# Ring_3_A.net
KiCad netlist of a schematic drawn in Altium Designer
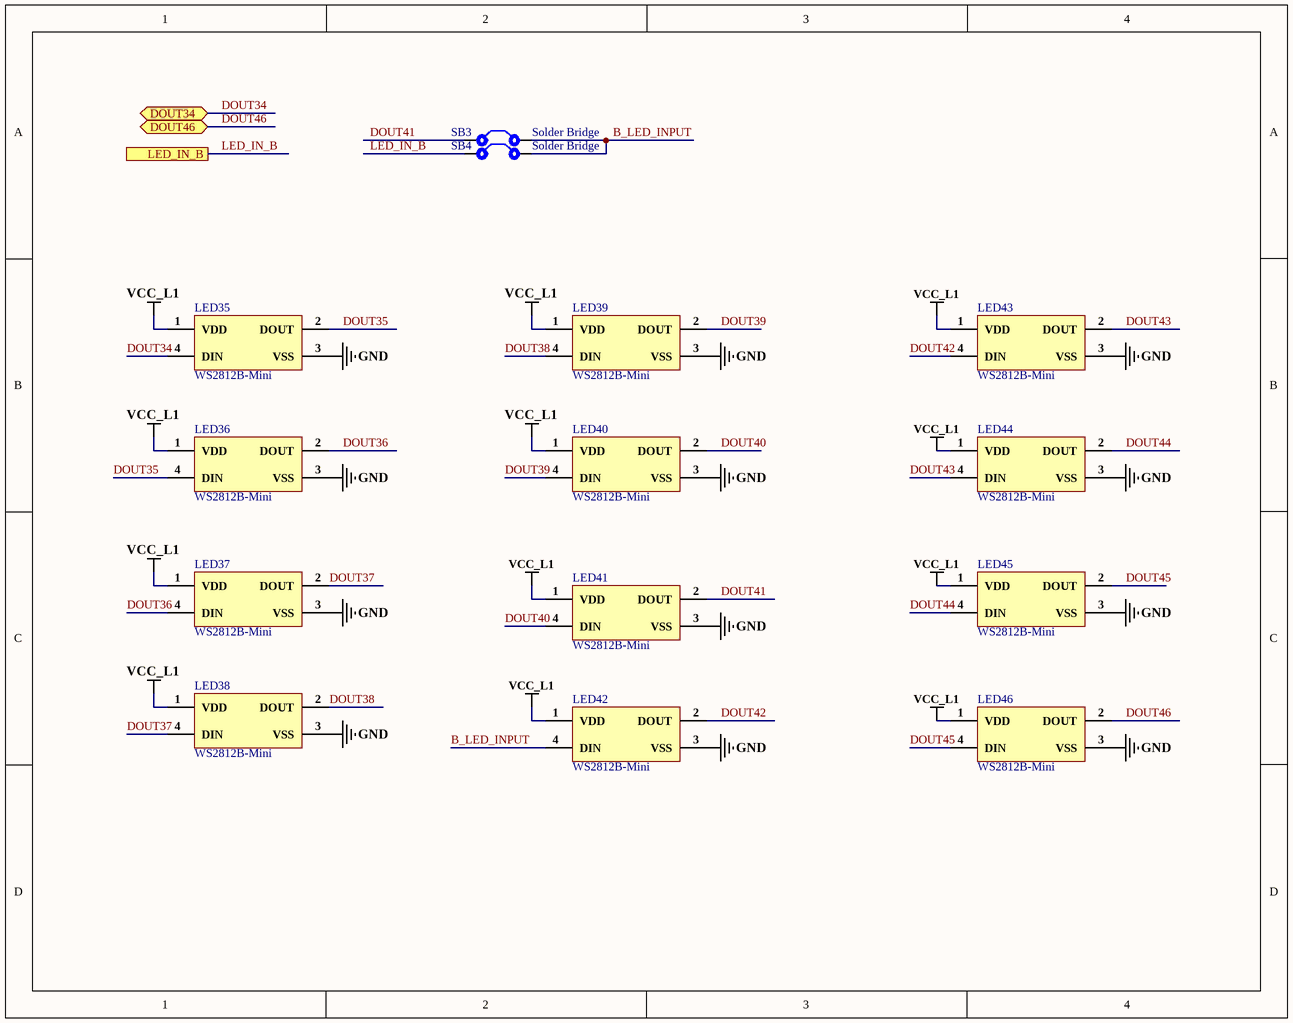
[diagram p0: Ring 3_A.SchDoc]

(export (version "E")
  (design (tool "Eeschema 10.0.6"))
  (components
    (comp (ref "LED35")
      (value "WS2812B-Mini")
      (footprint "WS2812B-Mini")
      (description "SMD,3.5x3.5mm Light Emitting Diodes (LED) RoHS")
      (fields (field (name "MANUFACTURER") "Worldsemi"))
      (libsource (lib "TT_IntLib") (part "WS2812B-Mini"))
    )
    (comp (ref "LED36")
      (value "WS2812B-Mini")
      (footprint "WS2812B-Mini")
      (description "SMD,3.5x3.5mm Light Emitting Diodes (LED) RoHS")
      (fields (field (name "MANUFACTURER") "Worldsemi"))
      (libsource (lib "TT_IntLib") (part "WS2812B-Mini"))
    )
    (comp (ref "LED37")
      (value "WS2812B-Mini")
      (footprint "WS2812B-Mini")
      (description "SMD,3.5x3.5mm Light Emitting Diodes (LED) RoHS")
      (fields (field (name "MANUFACTURER") "Worldsemi"))
      (libsource (lib "TT_IntLib") (part "WS2812B-Mini"))
    )
    (comp (ref "LED38")
      (value "WS2812B-Mini")
      (footprint "WS2812B-Mini")
      (description "SMD,3.5x3.5mm Light Emitting Diodes (LED) RoHS")
      (fields (field (name "MANUFACTURER") "Worldsemi"))
      (libsource (lib "TT_IntLib") (part "WS2812B-Mini"))
    )
    (comp (ref "LED39")
      (value "WS2812B-Mini")
      (footprint "WS2812B-Mini")
      (description "SMD,3.5x3.5mm Light Emitting Diodes (LED) RoHS")
      (fields (field (name "MANUFACTURER") "Worldsemi"))
      (libsource (lib "TT_IntLib") (part "WS2812B-Mini"))
    )
    (comp (ref "LED40")
      (value "WS2812B-Mini")
      (footprint "WS2812B-Mini")
      (description "SMD,3.5x3.5mm Light Emitting Diodes (LED) RoHS")
      (fields (field (name "MANUFACTURER") "Worldsemi"))
      (libsource (lib "TT_IntLib") (part "WS2812B-Mini"))
    )
    (comp (ref "LED41")
      (value "WS2812B-Mini")
      (footprint "WS2812B-Mini")
      (description "SMD,3.5x3.5mm Light Emitting Diodes (LED) RoHS")
      (fields (field (name "MANUFACTURER") "Worldsemi"))
      (libsource (lib "TT_IntLib") (part "WS2812B-Mini"))
    )
    (comp (ref "LED42")
      (value "WS2812B-Mini")
      (footprint "WS2812B-Mini")
      (description "SMD,3.5x3.5mm Light Emitting Diodes (LED) RoHS")
      (fields (field (name "MANUFACTURER") "Worldsemi"))
      (libsource (lib "TT_IntLib") (part "WS2812B-Mini"))
    )
    (comp (ref "LED43")
      (value "WS2812B-Mini")
      (footprint "WS2812B-Mini")
      (description "SMD,3.5x3.5mm Light Emitting Diodes (LED) RoHS")
      (fields (field (name "MANUFACTURER") "Worldsemi"))
      (libsource (lib "TT_IntLib") (part "WS2812B-Mini"))
    )
    (comp (ref "LED44")
      (value "WS2812B-Mini")
      (footprint "WS2812B-Mini")
      (description "SMD,3.5x3.5mm Light Emitting Diodes (LED) RoHS")
      (fields (field (name "MANUFACTURER") "Worldsemi"))
      (libsource (lib "TT_IntLib") (part "WS2812B-Mini"))
    )
    (comp (ref "LED45")
      (value "WS2812B-Mini")
      (footprint "WS2812B-Mini")
      (description "SMD,3.5x3.5mm Light Emitting Diodes (LED) RoHS")
      (fields (field (name "MANUFACTURER") "Worldsemi"))
      (libsource (lib "TT_IntLib") (part "WS2812B-Mini"))
    )
    (comp (ref "LED46")
      (value "WS2812B-Mini")
      (footprint "WS2812B-Mini")
      (description "SMD,3.5x3.5mm Light Emitting Diodes (LED) RoHS")
      (fields (field (name "MANUFACTURER") "Worldsemi"))
      (libsource (lib "TT_IntLib") (part "WS2812B-Mini"))
    )
    (comp (ref "SB3")
      (value "Solder Bridge")
      (footprint "Solder Bridge")
      (description "Solder Bridge ON")
      (libsource (lib "TT_IntLib") (part "Solder Bridge"))
    )
    (comp (ref "SB4")
      (value "Solder Bridge")
      (footprint "Solder Bridge")
      (description "Solder Bridge ON")
      (libsource (lib "TT_IntLib") (part "Solder Bridge"))
    )
  )
  (nets
    (net (code "1") (name "/B_LED_INPUT") (class "Default")
      (node (ref "LED42") (pin "4") (pinfunction "DIN_4") (pintype "passive"))
      (node (ref "SB3") (pin "2") (pinfunction "2_2") (pintype "passive"))
      (node (ref "SB4") (pin "2") (pinfunction "2_2") (pintype "passive"))
    )
    (net (code "2") (name "/DOUT34") (class "Default")
      (node (ref "LED35") (pin "4") (pinfunction "DIN_4") (pintype "passive"))
    )
    (net (code "3") (name "/DOUT35") (class "Default")
      (node (ref "LED35") (pin "2") (pinfunction "DOUT_2") (pintype "passive"))
      (node (ref "LED36") (pin "4") (pinfunction "DIN_4") (pintype "passive"))
    )
    (net (code "4") (name "/DOUT36") (class "Default")
      (node (ref "LED36") (pin "2") (pinfunction "DOUT_2") (pintype "passive"))
      (node (ref "LED37") (pin "4") (pinfunction "DIN_4") (pintype "passive"))
    )
    (net (code "5") (name "/DOUT37") (class "Default")
      (node (ref "LED37") (pin "2") (pinfunction "DOUT_2") (pintype "passive"))
      (node (ref "LED38") (pin "4") (pinfunction "DIN_4") (pintype "passive"))
    )
    (net (code "6") (name "/DOUT38") (class "Default")
      (node (ref "LED38") (pin "2") (pinfunction "DOUT_2") (pintype "passive"))
      (node (ref "LED39") (pin "4") (pinfunction "DIN_4") (pintype "passive"))
    )
    (net (code "7") (name "/DOUT39") (class "Default")
      (node (ref "LED39") (pin "2") (pinfunction "DOUT_2") (pintype "passive"))
      (node (ref "LED40") (pin "4") (pinfunction "DIN_4") (pintype "passive"))
    )
    (net (code "8") (name "/DOUT40") (class "Default")
      (node (ref "LED40") (pin "2") (pinfunction "DOUT_2") (pintype "passive"))
      (node (ref "LED41") (pin "4") (pinfunction "DIN_4") (pintype "passive"))
    )
    (net (code "9") (name "/DOUT41") (class "Default")
      (node (ref "LED41") (pin "2") (pinfunction "DOUT_2") (pintype "passive"))
      (node (ref "SB3") (pin "1") (pinfunction "1_1") (pintype "passive"))
    )
    (net (code "10") (name "/DOUT42") (class "Default")
      (node (ref "LED42") (pin "2") (pinfunction "DOUT_2") (pintype "passive"))
      (node (ref "LED43") (pin "4") (pinfunction "DIN_4") (pintype "passive"))
    )
    (net (code "11") (name "/DOUT43") (class "Default")
      (node (ref "LED43") (pin "2") (pinfunction "DOUT_2") (pintype "passive"))
      (node (ref "LED44") (pin "4") (pinfunction "DIN_4") (pintype "passive"))
    )
    (net (code "12") (name "/DOUT44") (class "Default")
      (node (ref "LED44") (pin "2") (pinfunction "DOUT_2") (pintype "passive"))
      (node (ref "LED45") (pin "4") (pinfunction "DIN_4") (pintype "passive"))
    )
    (net (code "13") (name "/DOUT45") (class "Default")
      (node (ref "LED45") (pin "2") (pinfunction "DOUT_2") (pintype "passive"))
      (node (ref "LED46") (pin "4") (pinfunction "DIN_4") (pintype "passive"))
    )
    (net (code "14") (name "/DOUT46") (class "Default")
      (node (ref "LED46") (pin "2") (pinfunction "DOUT_2") (pintype "passive"))
    )
    (net (code "15") (name "/LED_IN_B") (class "Default")
      (node (ref "SB4") (pin "1") (pinfunction "1_1") (pintype "passive"))
    )
    (net (code "16") (name "GND") (class "Default")
      (node (ref "LED35") (pin "3") (pinfunction "VSS_3") (pintype "passive"))
      (node (ref "LED36") (pin "3") (pinfunction "VSS_3") (pintype "passive"))
      (node (ref "LED37") (pin "3") (pinfunction "VSS_3") (pintype "passive"))
      (node (ref "LED38") (pin "3") (pinfunction "VSS_3") (pintype "passive"))
      (node (ref "LED39") (pin "3") (pinfunction "VSS_3") (pintype "passive"))
      (node (ref "LED40") (pin "3") (pinfunction "VSS_3") (pintype "passive"))
      (node (ref "LED41") (pin "3") (pinfunction "VSS_3") (pintype "passive"))
      (node (ref "LED42") (pin "3") (pinfunction "VSS_3") (pintype "passive"))
      (node (ref "LED43") (pin "3") (pinfunction "VSS_3") (pintype "passive"))
      (node (ref "LED44") (pin "3") (pinfunction "VSS_3") (pintype "passive"))
      (node (ref "LED45") (pin "3") (pinfunction "VSS_3") (pintype "passive"))
      (node (ref "LED46") (pin "3") (pinfunction "VSS_3") (pintype "passive"))
    )
    (net (code "17") (name "VCC_L1") (class "Default")
      (node (ref "LED35") (pin "1") (pinfunction "VDD_1") (pintype "passive"))
      (node (ref "LED36") (pin "1") (pinfunction "VDD_1") (pintype "passive"))
      (node (ref "LED37") (pin "1") (pinfunction "VDD_1") (pintype "passive"))
      (node (ref "LED38") (pin "1") (pinfunction "VDD_1") (pintype "passive"))
      (node (ref "LED39") (pin "1") (pinfunction "VDD_1") (pintype "passive"))
      (node (ref "LED40") (pin "1") (pinfunction "VDD_1") (pintype "passive"))
      (node (ref "LED41") (pin "1") (pinfunction "VDD_1") (pintype "passive"))
      (node (ref "LED42") (pin "1") (pinfunction "VDD_1") (pintype "passive"))
      (node (ref "LED43") (pin "1") (pinfunction "VDD_1") (pintype "passive"))
      (node (ref "LED44") (pin "1") (pinfunction "VDD_1") (pintype "passive"))
      (node (ref "LED45") (pin "1") (pinfunction "VDD_1") (pintype "passive"))
      (node (ref "LED46") (pin "1") (pinfunction "VDD_1") (pintype "passive"))
    )
  )
)
